# gas_sensor_childboard_v1.net
KiCad netlist of a schematic drawn in EAGLE
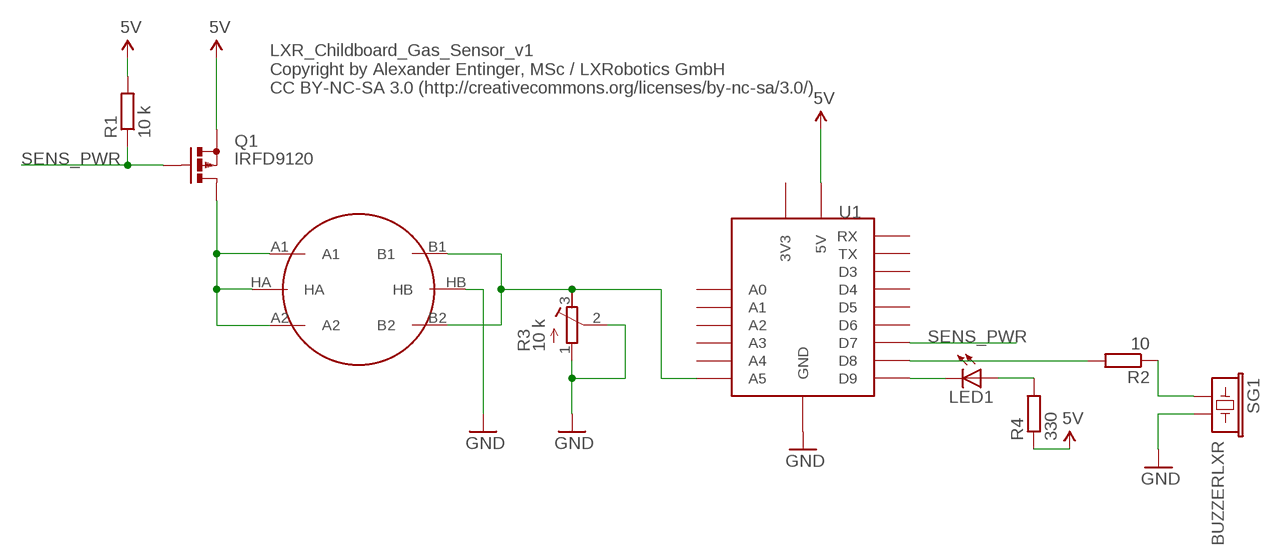
[diagram p0: schematic, sheet 1]

(export (version "E")
  (design (tool "Eeschema 10.0.6"))
  (components
    (comp (ref "LED1")
      (value "5 mm RED")
      (footprint "eagle-import:LED5MM")
      (libsource (lib "eagle-import") (part "LED5MM"))
    )
    (comp (ref "MQ-2")
      (value "METHANE_SENSOR")
      (footprint "eagle-import:MQ-3")
      (libsource (lib "eagle-import") (part "METHANE_SENSOR"))
    )
    (comp (ref "Q1")
      (value "IRFD9120")
      (footprint "eagle-import:C370-01")
      (libsource (lib "eagle-import") (part "IRFD9120"))
    )
    (comp (ref "R1")
      (value "10 k")
      (footprint "eagle-import:0207_7")
      (libsource (lib "eagle-import") (part "R-EU_0207/7"))
    )
    (comp (ref "R2")
      (value "10")
      (footprint "eagle-import:0207_7")
      (libsource (lib "eagle-import") (part "R-EU_0207/7"))
    )
    (comp (ref "R3")
      (value "10 k")
      (footprint "eagle-import:RTRIM3339P")
      (libsource (lib "eagle-import") (part "R-TRIMM3339P"))
    )
    (comp (ref "R4")
      (value "330")
      (footprint "eagle-import:0207_7")
      (libsource (lib "eagle-import") (part "R-EU_0207/7"))
    )
    (comp (ref "SG1")
      (value "BUZZERLXR")
      (footprint "eagle-import:BUZZER_LXR")
      (libsource (lib "eagle-import") (part "BUZZERLXR"))
    )
    (comp (ref "U1")
      (value "RF_CHILDBOARD_CONRF_C")
      (footprint "eagle-import:RF_CHILDBOARD_CON")
      (libsource (lib "eagle-import") (part "RF_CHILDBOARD_CONRF_C"))
    )
  )
  (nets
    (net (code "1") (name "/SENS_PWR") (class "Default")
      (node (ref "Q1") (pin "G") (pinfunction "G_G") (pintype "passive"))
      (node (ref "R1") (pin "1") (pinfunction "1_1") (pintype "passive"))
      (node (ref "U1") (pin "D7") (pinfunction "D7_D7") (pintype "bidirectional"))
    )
    (net (code "2") (name "5V") (class "Default")
      (node (ref "Q1") (pin "S") (pinfunction "S_S") (pintype "passive"))
      (node (ref "R1") (pin "2") (pinfunction "2_2") (pintype "passive"))
      (node (ref "R4") (pin "1") (pinfunction "1_1") (pintype "passive"))
      (node (ref "U1") (pin "5V") (pinfunction "5V_5V") (pintype "bidirectional"))
    )
    (net (code "3") (name "GND") (class "Default")
      (node (ref "MQ-2") (pin "HB") (pinfunction "HB_HB") (pintype "bidirectional"))
      (node (ref "R3") (pin "1") (pinfunction "E_1") (pintype "passive"))
      (node (ref "R3") (pin "2") (pinfunction "S_2") (pintype "passive"))
      (node (ref "SG1") (pin "2") (pinfunction "2_2") (pintype "passive"))
      (node (ref "U1") (pin "GND") (pinfunction "GND_GND") (pintype "bidirectional"))
      (node (ref "U1") (pin "GND1") (pinfunction "GND_GND1") (pintype "bidirectional"))
      (node (ref "U1") (pin "GND2") (pinfunction "GND_GND2") (pintype "bidirectional"))
    )
    (net (code "4") (name "Net-(LED1-C)") (class "Default")
      (node (ref "LED1") (pin "K") (pinfunction "C_K") (pintype "passive"))
      (node (ref "U1") (pin "D9") (pinfunction "D9_D9") (pintype "bidirectional"))
    )
    (net (code "5") (name "Net-(LED1-PadA)") (class "Default")
      (node (ref "LED1") (pin "A") (pinfunction "A_A") (pintype "passive"))
      (node (ref "R4") (pin "2") (pinfunction "2_2") (pintype "passive"))
    )
    (net (code "6") (name "Net-(MQ-2-PadA1)") (class "Default")
      (node (ref "MQ-2") (pin "A1") (pinfunction "A1_A1") (pintype "bidirectional"))
      (node (ref "MQ-2") (pin "A2") (pinfunction "A2_A2") (pintype "bidirectional"))
      (node (ref "MQ-2") (pin "HA") (pinfunction "HA_HA") (pintype "bidirectional"))
      (node (ref "Q1") (pin "D") (pinfunction "D_D") (pintype "passive"))
      (node (ref "Q1") (pin "D1") (pinfunction "D_D1") (pintype "passive"))
    )
    (net (code "7") (name "Net-(R2-Pad1)") (class "Default")
      (node (ref "R2") (pin "1") (pinfunction "1_1") (pintype "passive"))
      (node (ref "SG1") (pin "1") (pinfunction "1_1") (pintype "passive"))
    )
    (net (code "8") (name "Net-(R2-Pad2)") (class "Default")
      (node (ref "R2") (pin "2") (pinfunction "2_2") (pintype "passive"))
      (node (ref "U1") (pin "D8") (pinfunction "D8_D8") (pintype "bidirectional"))
    )
    (net (code "9") (name "Net-(R3-A)") (class "Default")
      (node (ref "MQ-2") (pin "B1") (pinfunction "B1_B1") (pintype "bidirectional"))
      (node (ref "MQ-2") (pin "B2") (pinfunction "B2_B2") (pintype "bidirectional"))
      (node (ref "R3") (pin "3") (pinfunction "A_3") (pintype "passive"))
      (node (ref "U1") (pin "A5") (pinfunction "A5_A5") (pintype "bidirectional"))
    )
    (net (code "10") (name "unconnected-(U1-Pad3V3)") (class "Default")
      (node (ref "U1") (pin "3V3") (pinfunction "3V3_3V3") (pintype "bidirectional"))
    )
    (net (code "11") (name "unconnected-(U1-PadA0)") (class "Default")
      (node (ref "U1") (pin "A0") (pinfunction "A0_A0") (pintype "bidirectional"))
    )
    (net (code "12") (name "unconnected-(U1-PadA1)") (class "Default")
      (node (ref "U1") (pin "A1") (pinfunction "A1_A1") (pintype "bidirectional"))
    )
    (net (code "13") (name "unconnected-(U1-PadA2)") (class "Default")
      (node (ref "U1") (pin "A2") (pinfunction "A2_A2") (pintype "bidirectional"))
    )
    (net (code "14") (name "unconnected-(U1-PadA3)") (class "Default")
      (node (ref "U1") (pin "A3") (pinfunction "A3_A3") (pintype "bidirectional"))
    )
    (net (code "15") (name "unconnected-(U1-PadA4)") (class "Default")
      (node (ref "U1") (pin "A4") (pinfunction "A4_A4") (pintype "bidirectional"))
    )
    (net (code "16") (name "unconnected-(U1-PadD3)") (class "Default")
      (node (ref "U1") (pin "D3") (pinfunction "D3_D3") (pintype "bidirectional"))
    )
    (net (code "17") (name "unconnected-(U1-PadD4)") (class "Default")
      (node (ref "U1") (pin "D4") (pinfunction "D4_D4") (pintype "bidirectional"))
    )
    (net (code "18") (name "unconnected-(U1-PadD5)") (class "Default")
      (node (ref "U1") (pin "D5") (pinfunction "D5_D5") (pintype "bidirectional"))
    )
    (net (code "19") (name "unconnected-(U1-PadD6)") (class "Default")
      (node (ref "U1") (pin "D6") (pinfunction "D6_D6") (pintype "bidirectional"))
    )
    (net (code "20") (name "unconnected-(U1-PadRX)") (class "Default")
      (node (ref "U1") (pin "RX") (pinfunction "RX_RX") (pintype "bidirectional"))
    )
    (net (code "21") (name "unconnected-(U1-PadTX)") (class "Default")
      (node (ref "U1") (pin "TX") (pinfunction "TX_TX") (pintype "bidirectional"))
    )
  )
)
